# ZYNQ_34_35_and_QPSI.net
KiCad netlist of a schematic drawn in Altium Designer
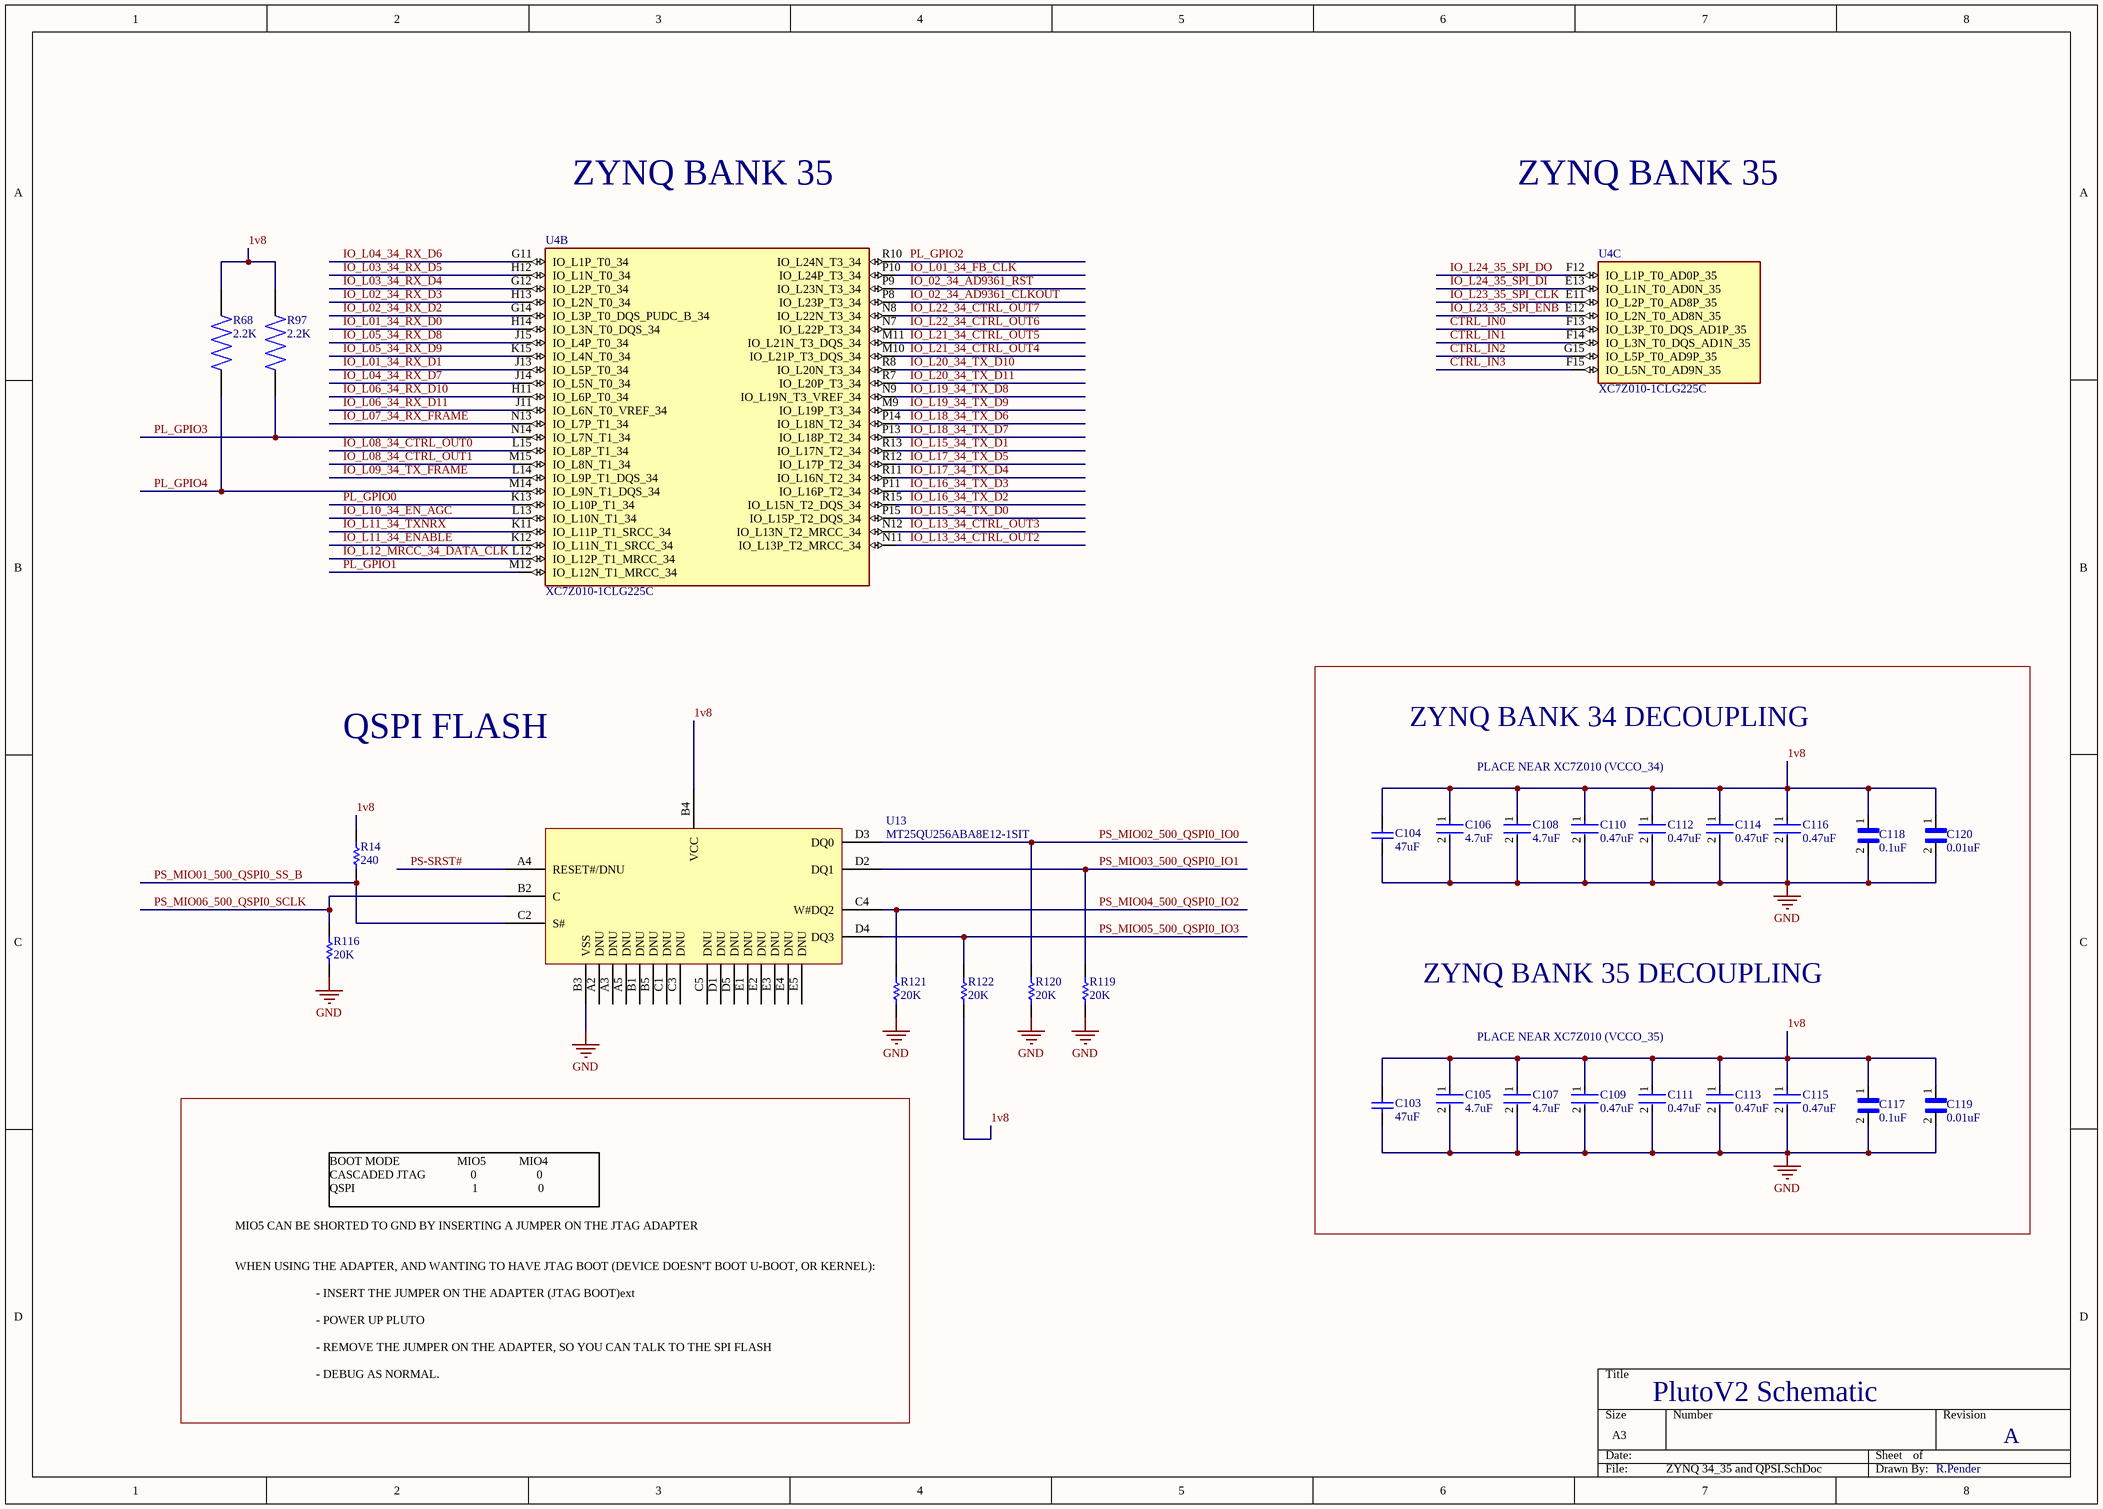
[diagram p0: ZYNQ 34_35 and QPSI.SchDoc]

(export (version "E")
  (design (tool "Eeschema 10.0.6"))
  (components
    (comp (ref "C103")
      (value "47uF")
      (footprint "TAYO-JMK212BBJ476MG-T_L")
      (fields
        (field (name "MANUFACTURER") "Taiyo Yuden")
        (field (name "TOLERANCE") "±20%")
        (field (name "PCN PART NUMBER") "X5R,X7RDielectrics23/Jan/2008")
      )
      (libsource (lib "Altium Content Vault") (part "CAP-NP-2"))
    )
    (comp (ref "C104")
      (value "47uF")
      (footprint "TAYO-JMK212BBJ476MG-T_L")
      (fields
        (field (name "MANUFACTURER") "Taiyo Yuden")
        (field (name "TOLERANCE") "±20%")
        (field (name "PCN PART NUMBER") "X5R,X7RDielectrics23/Jan/2008")
      )
      (libsource (lib "Altium Content Vault") (part "CAP-NP-2"))
    )
    (comp (ref "C105")
      (value "4.7uF")
      (footprint "FP-C1005-050-0_15-IPC_C")
      (description "CAP CER 4.7UF 6.3V X5R 0402")
      (fields (field (name "VOLTAGE") "6.3V") (field (name "TOLERANCE") "10%"))
      (libsource (lib "Altium Content Vault") (part "02cd4be3c70576c341d710602a673aa"))
    )
    (comp (ref "C106")
      (value "4.7uF")
      (footprint "FP-C1005-050-0_15-IPC_C")
      (description "CAP CER 4.7UF 6.3V X5R 0402")
      (fields (field (name "VOLTAGE") "6.3V") (field (name "TOLERANCE") "10%"))
      (libsource (lib "Altium Content Vault") (part "02cd4be3c70576c341d710602a673aa"))
    )
    (comp (ref "C107")
      (value "4.7uF")
      (footprint "FP-C1005-050-0_15-IPC_C")
      (description "CAP CER 4.7UF 6.3V X5R 0402")
      (fields (field (name "VOLTAGE") "6.3V") (field (name "TOLERANCE") "10%"))
      (libsource (lib "Altium Content Vault") (part "02cd4be3c70576c341d710602a673aa"))
    )
    (comp (ref "C108")
      (value "4.7uF")
      (footprint "FP-C1005-050-0_15-IPC_C")
      (description "CAP CER 4.7UF 6.3V X5R 0402")
      (fields (field (name "VOLTAGE") "6.3V") (field (name "TOLERANCE") "10%"))
      (libsource (lib "Altium Content Vault") (part "02cd4be3c70576c341d710602a673aa"))
    )
    (comp (ref "C109")
      (value "0.47uF")
      (footprint "FP-C1005-050-0_15-MFG")
      (description "CAP CER 4.7UF 6.3V X5R 0402")
      (fields (field (name "VOLTAGE") "6.3V") (field (name "TOLERANCE") "10%"))
      (libsource (lib "Altium Content Vault") (part "02cd4be3c70576c341d710602a673aa"))
    )
    (comp (ref "C110")
      (value "0.47uF")
      (footprint "FP-C1005-050-0_15-MFG")
      (description "CAP CER 4.7UF 6.3V X5R 0402")
      (fields (field (name "VOLTAGE") "6.3V") (field (name "TOLERANCE") "10%"))
      (libsource (lib "Altium Content Vault") (part "02cd4be3c70576c341d710602a673aa"))
    )
    (comp (ref "C111")
      (value "0.47uF")
      (footprint "FP-C1005-050-0_15-MFG")
      (description "CAP CER 4.7UF 6.3V X5R 0402")
      (fields (field (name "VOLTAGE") "6.3V") (field (name "TOLERANCE") "10%"))
      (libsource (lib "Altium Content Vault") (part "02cd4be3c70576c341d710602a673aa"))
    )
    (comp (ref "C112")
      (value "0.47uF")
      (footprint "FP-C1005-050-0_15-MFG")
      (description "CAP CER 4.7UF 6.3V X5R 0402")
      (fields (field (name "VOLTAGE") "6.3V") (field (name "TOLERANCE") "10%"))
      (libsource (lib "Altium Content Vault") (part "02cd4be3c70576c341d710602a673aa"))
    )
    (comp (ref "C113")
      (value "0.47uF")
      (footprint "FP-C1005-050-0_15-MFG")
      (description "CAP CER 4.7UF 6.3V X5R 0402")
      (fields (field (name "VOLTAGE") "6.3V") (field (name "TOLERANCE") "10%"))
      (libsource (lib "Altium Content Vault") (part "02cd4be3c70576c341d710602a673aa"))
    )
    (comp (ref "C114")
      (value "0.47uF")
      (footprint "FP-C1005-050-0_15-MFG")
      (description "CAP CER 4.7UF 6.3V X5R 0402")
      (fields (field (name "VOLTAGE") "6.3V") (field (name "TOLERANCE") "10%"))
      (libsource (lib "Altium Content Vault") (part "02cd4be3c70576c341d710602a673aa"))
    )
    (comp (ref "C115")
      (value "0.47uF")
      (footprint "FP-C1005-050-0_15-MFG")
      (description "CAP CER 4.7UF 6.3V X5R 0402")
      (fields (field (name "VOLTAGE") "6.3V") (field (name "TOLERANCE") "10%"))
      (libsource (lib "Altium Content Vault") (part "02cd4be3c70576c341d710602a673aa"))
    )
    (comp (ref "C116")
      (value "0.47uF")
      (footprint "FP-C1005-050-0_15-MFG")
      (description "CAP CER 4.7UF 6.3V X5R 0402")
      (fields (field (name "VOLTAGE") "6.3V") (field (name "TOLERANCE") "10%"))
      (libsource (lib "Altium Content Vault") (part "02cd4be3c70576c341d710602a673aa"))
    )
    (comp (ref "C117")
      (value "0.1uF")
      (footprint "CAPC0603X33N")
      (description "CAP 0.1UF 16VDC X5R 20% SMD 0201 PAPER TAPE")
      (fields (field (name "MP") "GRM033R61C104ME84D"))
      (libsource (lib "GRM033R61C104ME84D") (part "GRM033R61C104ME84D"))
    )
    (comp (ref "C118")
      (value "0.1uF")
      (footprint "CAPC0603X33N")
      (description "CAP 0.1UF 16VDC X5R 20% SMD 0201 PAPER TAPE")
      (fields (field (name "MP") "GRM033R61C104ME84D"))
      (libsource (lib "GRM033R61C104ME84D") (part "GRM033R61C104ME84D"))
    )
    (comp (ref "C119")
      (value "0.01uF")
      (footprint "CAPC0603X33N")
      (description "SMD Capacitor X7R(EIA) with Capacitance: 10000pF Tol. 10%. Rated Voltage: 10Vdc")
      (fields (field (name "MP") "GRM033R71A103KA01D") (field (name "MF") "Murata"))
      (libsource (lib "GRM033R71A103KA01D") (part "GRM033R71A103KA01D"))
    )
    (comp (ref "C120")
      (value "0.01uF")
      (footprint "CAPC0603X33N")
      (description "SMD Capacitor X7R(EIA) with Capacitance: 10000pF Tol. 10%. Rated Voltage: 10Vdc")
      (fields (field (name "MP") "GRM033R71A103KA01D") (field (name "MF") "Murata"))
      (libsource (lib "GRM033R71A103KA01D") (part "GRM033R71A103KA01D"))
    )
    (comp (ref "R14")
      (value "240")
      (footprint "2-0402")
      (fields (field (name "PUBLISHER") "Altium Limited"))
      (libsource (lib "Panasonic Resistor") (part "ERJ2RK"))
    )
    (comp (ref "R68")
      (value "2.2K")
      (footprint "RESC1005X35N")
      (description "2.2 kOhms Â±1% 0.063W, 1/16W Chip Resistor 0402 _1005 Metric_ Thick Film")
      (fields (field (name "MF") "Vishay") (field (name "MP") "CRCW04022K20FKEDC"))
      (libsource (lib "CRCW04022K20FKEDC") (part "CRCW04022K20FKEDC"))
    )
    (comp (ref "R97")
      (value "2.2K")
      (footprint "RESC1005X35N")
      (description "2.2 kOhms Â±1% 0.063W, 1/16W Chip Resistor 0402 _1005 Metric_ Thick Film")
      (fields (field (name "MF") "Vishay") (field (name "MP") "CRCW04022K20FKEDC"))
      (libsource (lib "CRCW04022K20FKEDC") (part "CRCW04022K20FKEDC"))
    )
    (comp (ref "R116")
      (value "20K")
      (footprint "2-0402")
      (fields (field (name "PUBLISHER") "Altium Limited"))
      (libsource (lib "Panasonic Resistor") (part "ERJ2RK"))
    )
    (comp (ref "R119")
      (value "20K")
      (footprint "2-0402")
      (fields (field (name "PUBLISHER") "Altium Limited"))
      (libsource (lib "Panasonic Resistor") (part "ERJ2RK"))
    )
    (comp (ref "R120")
      (value "20K")
      (footprint "2-0402")
      (fields (field (name "PUBLISHER") "Altium Limited"))
      (libsource (lib "Panasonic Resistor") (part "ERJ2RK"))
    )
    (comp (ref "R121")
      (value "20K")
      (footprint "2-0402")
      (fields (field (name "PUBLISHER") "Altium Limited"))
      (libsource (lib "Panasonic Resistor") (part "ERJ2RK"))
    )
    (comp (ref "R122")
      (value "20K")
      (footprint "2-0402")
      (fields (field (name "PUBLISHER") "Altium Limited"))
      (libsource (lib "Panasonic Resistor") (part "ERJ2RK"))
    )
    (comp (ref "U4")
      (value "XC7Z010-1CLG225C")
      (footprint "BGA225C80P15X15_1300X1300X150")
      (fields (field (name "MF") "Xilinx Inc.") (field (name "DIGI-KEY_PART_NUMBER") "122-1855-ND"))
      (libsource (lib "XC7Z010-1CLG225C") (part "XC7Z010-1CLG225C"))
    )
    (comp (ref "U13")
      (value "MT25QU256ABA8E12-1SIT")
      (footprint "BGA25C100P5X5_800X600X120N")
      (libsource (lib "RINALDOSCHEMS") (part "Component_1"))
    )
  )
  (nets
    (net (code "1") (name "/1v8") (class "Default")
      (node (ref "C103") (pin "1") (pinfunction "1_1") (pintype "passive"))
      (node (ref "C104") (pin "1") (pinfunction "1_1") (pintype "passive"))
      (node (ref "C105") (pin "1") (pinfunction "1_1") (pintype "passive"))
      (node (ref "C106") (pin "1") (pinfunction "1_1") (pintype "passive"))
      (node (ref "C107") (pin "1") (pinfunction "1_1") (pintype "passive"))
      (node (ref "C108") (pin "1") (pinfunction "1_1") (pintype "passive"))
      (node (ref "C109") (pin "1") (pinfunction "1_1") (pintype "passive"))
      (node (ref "C110") (pin "1") (pinfunction "1_1") (pintype "passive"))
      (node (ref "C111") (pin "1") (pinfunction "1_1") (pintype "passive"))
      (node (ref "C112") (pin "1") (pinfunction "1_1") (pintype "passive"))
      (node (ref "C113") (pin "1") (pinfunction "1_1") (pintype "passive"))
      (node (ref "C114") (pin "1") (pinfunction "1_1") (pintype "passive"))
      (node (ref "C115") (pin "1") (pinfunction "1_1") (pintype "passive"))
      (node (ref "C116") (pin "1") (pinfunction "1_1") (pintype "passive"))
      (node (ref "C117") (pin "1") (pinfunction "1_1") (pintype "passive"))
      (node (ref "C118") (pin "1") (pinfunction "1_1") (pintype "passive"))
      (node (ref "C119") (pin "1") (pinfunction "1_1") (pintype "passive"))
      (node (ref "C120") (pin "1") (pinfunction "1_1") (pintype "passive"))
      (node (ref "R122") (pin "2") (pinfunction "2_2") (pintype "passive"))
      (node (ref "R14") (pin "1") (pinfunction "1_1") (pintype "passive"))
      (node (ref "R68") (pin "2") (pinfunction "2_2") (pintype "passive"))
      (node (ref "R97") (pin "2") (pinfunction "2_2") (pintype "passive"))
      (node (ref "U13") (pin "B4") (pinfunction "VCC_B4") (pintype "power_in"))
    )
    (net (code "2") (name "/CTRL_IN0") (class "Default")
      (node (ref "U4") (pin "F13") (pinfunction "IO_L3P_T0_DQS_AD1P_35_F13") (pintype "bidirectional"))
    )
    (net (code "3") (name "/CTRL_IN1") (class "Default")
      (node (ref "U4") (pin "F14") (pinfunction "IO_L3N_T0_DQS_AD1N_35_F14") (pintype "bidirectional"))
    )
    (net (code "4") (name "/CTRL_IN2") (class "Default")
      (node (ref "U4") (pin "G15") (pinfunction "IO_L5P_T0_AD9P_35_G15") (pintype "bidirectional"))
    )
    (net (code "5") (name "/CTRL_IN3") (class "Default")
      (node (ref "U4") (pin "F15") (pinfunction "IO_L5N_T0_AD9N_35_F15") (pintype "bidirectional"))
    )
    (net (code "6") (name "/IO_02_34_AD9361_CLKOUT") (class "Default")
      (node (ref "U4") (pin "P8") (pinfunction "IO_L23P_T3_34_P8") (pintype "bidirectional"))
    )
    (net (code "7") (name "/IO_02_34_AD9361_RST") (class "Default")
      (node (ref "U4") (pin "P9") (pinfunction "IO_L23N_T3_34_P9") (pintype "bidirectional"))
    )
    (net (code "8") (name "/IO_L01_34_FB_CLK") (class "Default")
      (node (ref "U4") (pin "P10") (pinfunction "IO_L24P_T3_34_P10") (pintype "bidirectional"))
    )
    (net (code "9") (name "/IO_L01_34_RX_D0") (class "Default")
      (node (ref "U4") (pin "H14") (pinfunction "IO_L3N_T0_DQS_34_H14") (pintype "bidirectional"))
    )
    (net (code "10") (name "/IO_L01_34_RX_D1") (class "Default")
      (node (ref "U4") (pin "J13") (pinfunction "IO_L5P_T0_34_J13") (pintype "bidirectional"))
    )
    (net (code "11") (name "/IO_L02_34_RX_D2") (class "Default")
      (node (ref "U4") (pin "G14") (pinfunction "IO_L3P_T0_DQS_PUDC_B_34_G14") (pintype "bidirectional"))
    )
    (net (code "12") (name "/IO_L02_34_RX_D3") (class "Default")
      (node (ref "U4") (pin "H13") (pinfunction "IO_L2N_T0_34_H13") (pintype "bidirectional"))
    )
    (net (code "13") (name "/IO_L03_34_RX_D4") (class "Default")
      (node (ref "U4") (pin "G12") (pinfunction "IO_L2P_T0_34_G12") (pintype "bidirectional"))
    )
    (net (code "14") (name "/IO_L03_34_RX_D5") (class "Default")
      (node (ref "U4") (pin "H12") (pinfunction "IO_L1N_T0_34_H12") (pintype "bidirectional"))
    )
    (net (code "15") (name "/IO_L04_34_RX_D6") (class "Default")
      (node (ref "U4") (pin "G11") (pinfunction "IO_L1P_T0_34_G11") (pintype "bidirectional"))
    )
    (net (code "16") (name "/IO_L04_34_RX_D7") (class "Default")
      (node (ref "U4") (pin "J14") (pinfunction "IO_L5N_T0_34_J14") (pintype "bidirectional"))
    )
    (net (code "17") (name "/IO_L05_34_RX_D8") (class "Default")
      (node (ref "U4") (pin "J15") (pinfunction "IO_L4P_T0_34_J15") (pintype "bidirectional"))
    )
    (net (code "18") (name "/IO_L05_34_RX_D9") (class "Default")
      (node (ref "U4") (pin "K15") (pinfunction "IO_L4N_T0_34_K15") (pintype "bidirectional"))
    )
    (net (code "19") (name "/IO_L06_34_RX_D10") (class "Default")
      (node (ref "U4") (pin "H11") (pinfunction "IO_L6P_T0_34_H11") (pintype "bidirectional"))
    )
    (net (code "20") (name "/IO_L06_34_RX_D11") (class "Default")
      (node (ref "U4") (pin "J11") (pinfunction "IO_L6N_T0_VREF_34_J11") (pintype "bidirectional"))
    )
    (net (code "21") (name "/IO_L07_34_RX_FRAME") (class "Default")
      (node (ref "U4") (pin "N13") (pinfunction "IO_L7P_T1_34_N13") (pintype "bidirectional"))
    )
    (net (code "22") (name "/IO_L08_34_CTRL_OUT0") (class "Default")
      (node (ref "U4") (pin "L15") (pinfunction "IO_L8P_T1_34_L15") (pintype "bidirectional"))
    )
    (net (code "23") (name "/IO_L08_34_CTRL_OUT1") (class "Default")
      (node (ref "U4") (pin "M15") (pinfunction "IO_L8N_T1_34_M15") (pintype "bidirectional"))
    )
    (net (code "24") (name "/IO_L09_34_TX_FRAME") (class "Default")
      (node (ref "U4") (pin "L14") (pinfunction "IO_L9P_T1_DQS_34_L14") (pintype "bidirectional"))
    )
    (net (code "25") (name "/IO_L10_34_EN_AGC") (class "Default")
      (node (ref "U4") (pin "L13") (pinfunction "IO_L10N_T1_34_L13") (pintype "bidirectional"))
    )
    (net (code "26") (name "/IO_L11_34_ENABLE") (class "Default")
      (node (ref "U4") (pin "K12") (pinfunction "IO_L11N_T1_SRCC_34_K12") (pintype "bidirectional"))
    )
    (net (code "27") (name "/IO_L11_34_TXNRX") (class "Default")
      (node (ref "U4") (pin "K11") (pinfunction "IO_L11P_T1_SRCC_34_K11") (pintype "bidirectional"))
    )
    (net (code "28") (name "/IO_L12_MRCC_34_DATA_CLK") (class "Default")
      (node (ref "U4") (pin "L12") (pinfunction "IO_L12P_T1_MRCC_34_L12") (pintype "bidirectional"))
    )
    (net (code "29") (name "/IO_L13_34_CTRL_OUT2") (class "Default")
      (node (ref "U4") (pin "N11") (pinfunction "IO_L13P_T2_MRCC_34_N11") (pintype "bidirectional"))
    )
    (net (code "30") (name "/IO_L13_34_CTRL_OUT3") (class "Default")
      (node (ref "U4") (pin "N12") (pinfunction "IO_L13N_T2_MRCC_34_N12") (pintype "bidirectional"))
    )
    (net (code "31") (name "/IO_L15_34_TX_D0") (class "Default")
      (node (ref "U4") (pin "P15") (pinfunction "IO_L15P_T2_DQS_34_P15") (pintype "bidirectional"))
    )
    (net (code "32") (name "/IO_L15_34_TX_D1") (class "Default")
      (node (ref "U4") (pin "R13") (pinfunction "IO_L17N_T2_34_R13") (pintype "bidirectional"))
    )
    (net (code "33") (name "/IO_L16_34_TX_D2") (class "Default")
      (node (ref "U4") (pin "R15") (pinfunction "IO_L15N_T2_DQS_34_R15") (pintype "bidirectional"))
    )
    (net (code "34") (name "/IO_L16_34_TX_D3") (class "Default")
      (node (ref "U4") (pin "P11") (pinfunction "IO_L16P_T2_34_P11") (pintype "bidirectional"))
    )
    (net (code "35") (name "/IO_L17_34_TX_D4") (class "Default")
      (node (ref "U4") (pin "R11") (pinfunction "IO_L16N_T2_34_R11") (pintype "bidirectional"))
    )
    (net (code "36") (name "/IO_L17_34_TX_D5") (class "Default")
      (node (ref "U4") (pin "R12") (pinfunction "IO_L17P_T2_34_R12") (pintype "bidirectional"))
    )
    (net (code "37") (name "/IO_L18_34_TX_D6") (class "Default")
      (node (ref "U4") (pin "P14") (pinfunction "IO_L18N_T2_34_P14") (pintype "bidirectional"))
    )
    (net (code "38") (name "/IO_L18_34_TX_D7") (class "Default")
      (node (ref "U4") (pin "P13") (pinfunction "IO_L18P_T2_34_P13") (pintype "bidirectional"))
    )
    (net (code "39") (name "/IO_L19_34_TX_D8") (class "Default")
      (node (ref "U4") (pin "N9") (pinfunction "IO_L19N_T3_VREF_34_N9") (pintype "bidirectional"))
    )
    (net (code "40") (name "/IO_L19_34_TX_D9") (class "Default")
      (node (ref "U4") (pin "M9") (pinfunction "IO_L19P_T3_34_M9") (pintype "bidirectional"))
    )
    (net (code "41") (name "/IO_L20_34_TX_D10") (class "Default")
      (node (ref "U4") (pin "R8") (pinfunction "IO_L20N_T3_34_R8") (pintype "bidirectional"))
    )
    (net (code "42") (name "/IO_L20_34_TX_D11") (class "Default")
      (node (ref "U4") (pin "R7") (pinfunction "IO_L20P_T3_34_R7") (pintype "bidirectional"))
    )
    (net (code "43") (name "/IO_L21_34_CTRL_OUT4") (class "Default")
      (node (ref "U4") (pin "M10") (pinfunction "IO_L21P_T3_DQS_34_M10") (pintype "bidirectional"))
    )
    (net (code "44") (name "/IO_L21_34_CTRL_OUT5") (class "Default")
      (node (ref "U4") (pin "M11") (pinfunction "IO_L21N_T3_DQS_34_M11") (pintype "bidirectional"))
    )
    (net (code "45") (name "/IO_L22_34_CTRL_OUT6") (class "Default")
      (node (ref "U4") (pin "N7") (pinfunction "IO_L22P_T3_34_N7") (pintype "bidirectional"))
    )
    (net (code "46") (name "/IO_L22_34_CTRL_OUT7") (class "Default")
      (node (ref "U4") (pin "N8") (pinfunction "IO_L22N_T3_34_N8") (pintype "bidirectional"))
    )
    (net (code "47") (name "/IO_L23_35_SPI_CLK") (class "Default")
      (node (ref "U4") (pin "E11") (pinfunction "IO_L2P_T0_AD8P_35_E11") (pintype "bidirectional"))
    )
    (net (code "48") (name "/IO_L23_35_SPI_ENB") (class "Default")
      (node (ref "U4") (pin "E12") (pinfunction "IO_L2N_T0_AD8N_35_E12") (pintype "bidirectional"))
    )
    (net (code "49") (name "/IO_L24_35_SPI_DI") (class "Default")
      (node (ref "U4") (pin "E13") (pinfunction "IO_L1N_T0_AD0N_35_E13") (pintype "bidirectional"))
    )
    (net (code "50") (name "/IO_L24_35_SPI_DO") (class "Default")
      (node (ref "U4") (pin "F12") (pinfunction "IO_L1P_T0_AD0P_35_F12") (pintype "bidirectional"))
    )
    (net (code "51") (name "/PL_GPIO0") (class "Default")
      (node (ref "U4") (pin "K13") (pinfunction "IO_L10P_T1_34_K13") (pintype "bidirectional"))
    )
    (net (code "52") (name "/PL_GPIO1") (class "Default")
      (node (ref "U4") (pin "M12") (pinfunction "IO_L12N_T1_MRCC_34_M12") (pintype "bidirectional"))
    )
    (net (code "53") (name "/PL_GPIO2") (class "Default")
      (node (ref "U4") (pin "R10") (pinfunction "IO_L24N_T3_34_R10") (pintype "bidirectional"))
    )
    (net (code "54") (name "/PL_GPIO3") (class "Default")
      (node (ref "R97") (pin "1") (pinfunction "1_1") (pintype "passive"))
      (node (ref "U4") (pin "N14") (pinfunction "IO_L7N_T1_34_N14") (pintype "bidirectional"))
    )
    (net (code "55") (name "/PL_GPIO4") (class "Default")
      (node (ref "R68") (pin "1") (pinfunction "1_1") (pintype "passive"))
      (node (ref "U4") (pin "M14") (pinfunction "IO_L9N_T1_DQS_34_M14") (pintype "bidirectional"))
    )
    (net (code "56") (name "/PS-SRST#") (class "Default")
      (node (ref "U13") (pin "A4") (pinfunction "RESET#/DNU_A4") (pintype "passive"))
    )
    (net (code "57") (name "/PS_MIO01_500_QSPI0_SS_B") (class "Default")
      (node (ref "R14") (pin "2") (pinfunction "2_2") (pintype "passive"))
      (node (ref "U13") (pin "C2") (pinfunction "S#_C2") (pintype "passive"))
    )
    (net (code "58") (name "/PS_MIO02_500_QSPI0_IO0") (class "Default")
      (node (ref "R120") (pin "1") (pinfunction "1_1") (pintype "passive"))
      (node (ref "U13") (pin "D3") (pinfunction "DQ0_D3") (pintype "passive"))
    )
    (net (code "59") (name "/PS_MIO03_500_QSPI0_IO1") (class "Default")
      (node (ref "R119") (pin "1") (pinfunction "1_1") (pintype "passive"))
      (node (ref "U13") (pin "D2") (pinfunction "DQ1_D2") (pintype "passive"))
    )
    (net (code "60") (name "/PS_MIO04_500_QSPI0_IO2") (class "Default")
      (node (ref "R121") (pin "1") (pinfunction "1_1") (pintype "passive"))
      (node (ref "U13") (pin "C4") (pinfunction "W#DQ2_C4") (pintype "passive"))
    )
    (net (code "61") (name "/PS_MIO05_500_QSPI0_IO3") (class "Default")
      (node (ref "R122") (pin "1") (pinfunction "1_1") (pintype "passive"))
      (node (ref "U13") (pin "D4") (pinfunction "DQ3_D4") (pintype "passive"))
    )
    (net (code "62") (name "/PS_MIO06_500_QSPI0_SCLK") (class "Default")
      (node (ref "R116") (pin "1") (pinfunction "1_1") (pintype "passive"))
      (node (ref "U13") (pin "B2") (pinfunction "C_B2") (pintype "passive"))
    )
    (net (code "63") (name "GND") (class "Default")
      (node (ref "C103") (pin "2") (pinfunction "2_2") (pintype "passive"))
      (node (ref "C104") (pin "2") (pinfunction "2_2") (pintype "passive"))
      (node (ref "C105") (pin "2") (pinfunction "2_2") (pintype "passive"))
      (node (ref "C106") (pin "2") (pinfunction "2_2") (pintype "passive"))
      (node (ref "C107") (pin "2") (pinfunction "2_2") (pintype "passive"))
      (node (ref "C108") (pin "2") (pinfunction "2_2") (pintype "passive"))
      (node (ref "C109") (pin "2") (pinfunction "2_2") (pintype "passive"))
      (node (ref "C110") (pin "2") (pinfunction "2_2") (pintype "passive"))
      (node (ref "C111") (pin "2") (pinfunction "2_2") (pintype "passive"))
      (node (ref "C112") (pin "2") (pinfunction "2_2") (pintype "passive"))
      (node (ref "C113") (pin "2") (pinfunction "2_2") (pintype "passive"))
      (node (ref "C114") (pin "2") (pinfunction "2_2") (pintype "passive"))
      (node (ref "C115") (pin "2") (pinfunction "2_2") (pintype "passive"))
      (node (ref "C116") (pin "2") (pinfunction "2_2") (pintype "passive"))
      (node (ref "C117") (pin "2") (pinfunction "2_2") (pintype "passive"))
      (node (ref "C118") (pin "2") (pinfunction "2_2") (pintype "passive"))
      (node (ref "C119") (pin "2") (pinfunction "2_2") (pintype "passive"))
      (node (ref "C120") (pin "2") (pinfunction "2_2") (pintype "passive"))
      (node (ref "R116") (pin "2") (pinfunction "2_2") (pintype "passive"))
      (node (ref "R119") (pin "2") (pinfunction "2_2") (pintype "passive"))
      (node (ref "R120") (pin "2") (pinfunction "2_2") (pintype "passive"))
      (node (ref "R121") (pin "2") (pinfunction "2_2") (pintype "passive"))
      (node (ref "U13") (pin "B3") (pinfunction "VSS_B3") (pintype "power_in"))
    )
    (net (code "64") (name "unconnected-(U13-DNU-PadA2)") (class "Default")
      (node (ref "U13") (pin "A2") (pinfunction "DNU_A2") (pintype "passive"))
    )
    (net (code "65") (name "unconnected-(U13-DNU-PadA3)") (class "Default")
      (node (ref "U13") (pin "A3") (pinfunction "DNU_A3") (pintype "passive"))
    )
    (net (code "66") (name "unconnected-(U13-DNU-PadA5)") (class "Default")
      (node (ref "U13") (pin "A5") (pinfunction "DNU_A5") (pintype "passive"))
    )
    (net (code "67") (name "unconnected-(U13-DNU-PadB1)") (class "Default")
      (node (ref "U13") (pin "B1") (pinfunction "DNU_B1") (pintype "passive"))
    )
    (net (code "68") (name "unconnected-(U13-DNU-PadB5)") (class "Default")
      (node (ref "U13") (pin "B5") (pinfunction "DNU_B5") (pintype "passive"))
    )
    (net (code "69") (name "unconnected-(U13-DNU-PadC1)") (class "Default")
      (node (ref "U13") (pin "C1") (pinfunction "DNU_C1") (pintype "passive"))
    )
    (net (code "70") (name "unconnected-(U13-DNU-PadC3)") (class "Default")
      (node (ref "U13") (pin "C3") (pinfunction "DNU_C3") (pintype "passive"))
    )
    (net (code "71") (name "unconnected-(U13-DNU-PadC5)") (class "Default")
      (node (ref "U13") (pin "C5") (pinfunction "DNU_C5") (pintype "passive"))
    )
    (net (code "72") (name "unconnected-(U13-DNU-PadD1)") (class "Default")
      (node (ref "U13") (pin "D1") (pinfunction "DNU_D1") (pintype "passive"))
    )
    (net (code "73") (name "unconnected-(U13-DNU-PadD5)") (class "Default")
      (node (ref "U13") (pin "D5") (pinfunction "DNU_D5") (pintype "passive"))
    )
    (net (code "74") (name "unconnected-(U13-DNU-PadE1)") (class "Default")
      (node (ref "U13") (pin "E1") (pinfunction "DNU_E1") (pintype "passive"))
    )
    (net (code "75") (name "unconnected-(U13-DNU-PadE2)") (class "Default")
      (node (ref "U13") (pin "E2") (pinfunction "DNU_E2") (pintype "passive"))
    )
    (net (code "76") (name "unconnected-(U13-DNU-PadE3)") (class "Default")
      (node (ref "U13") (pin "E3") (pinfunction "DNU_E3") (pintype "passive"))
    )
    (net (code "77") (name "unconnected-(U13-DNU-PadE4)") (class "Default")
      (node (ref "U13") (pin "E4") (pinfunction "DNU_E4") (pintype "passive"))
    )
    (net (code "78") (name "unconnected-(U13-DNU-PadE5)") (class "Default")
      (node (ref "U13") (pin "E5") (pinfunction "DNU_E5") (pintype "passive"))
    )
  )
)
